# Charge_Discharge_Battery_Monitor_DC_DC_B.net
KiCad netlist of a schematic drawn in Altium Designer
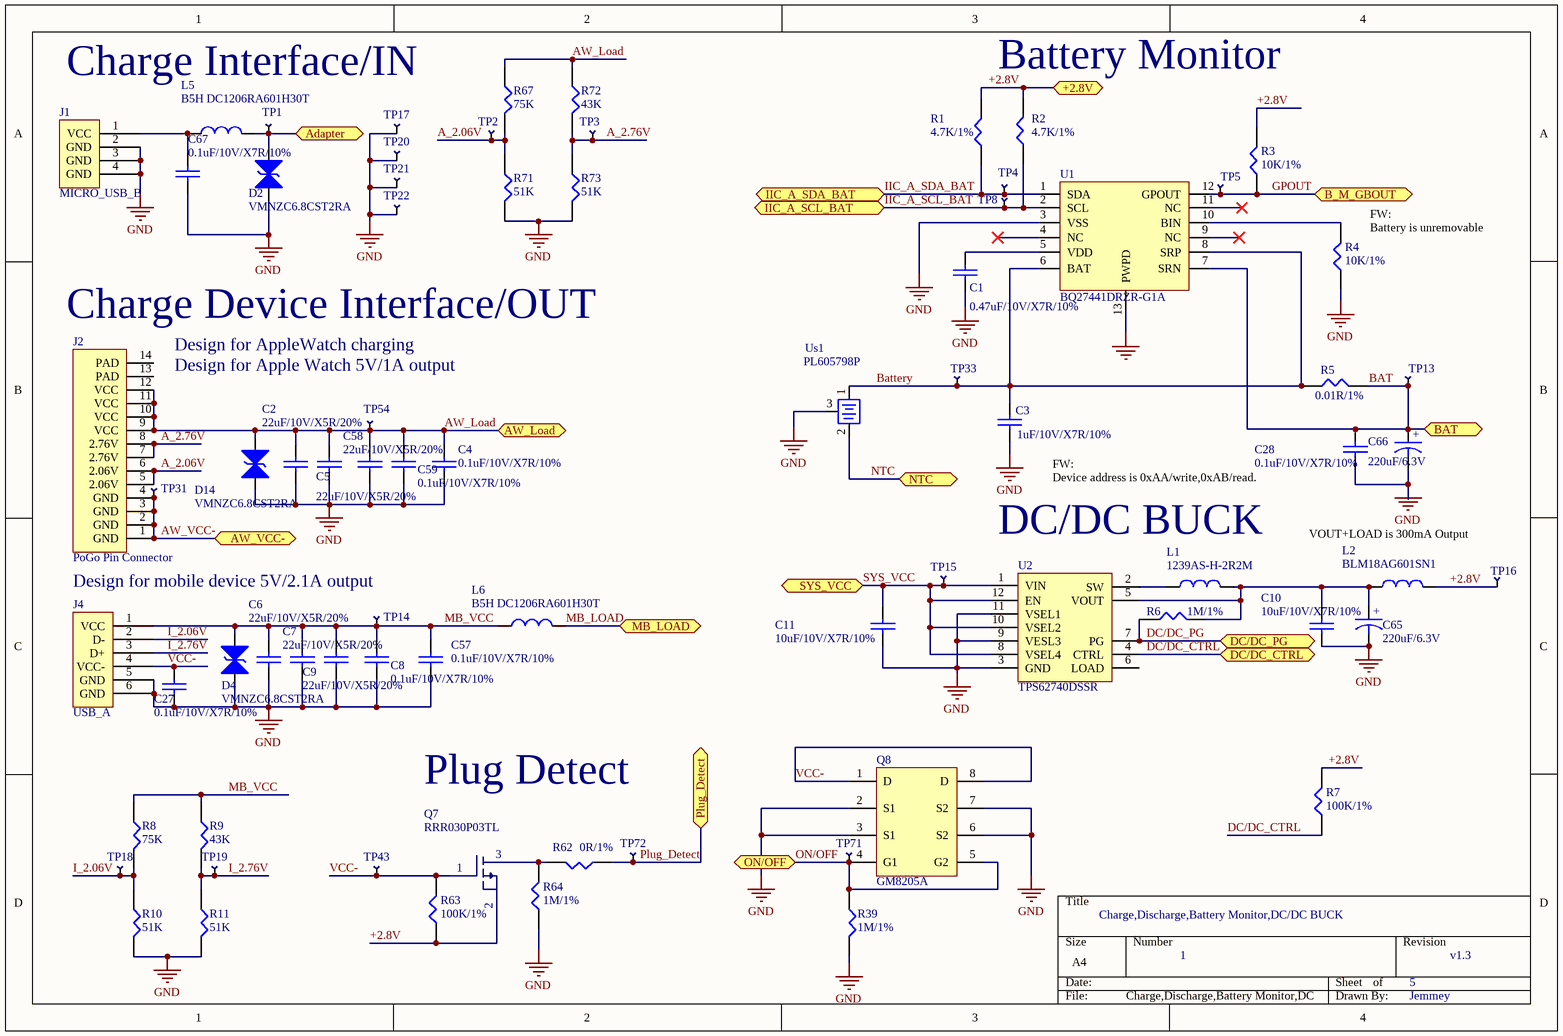
[diagram p0: Charge,Discharge,Battery Monitor,DC DC BUCK.SchDoc]

(export (version "E")
  (design (tool "Eeschema 10.0.6"))
  (components
    (comp (ref "C1")
      (value "0.47uF/10V/X7R/10%")
      (footprint "0402C")
      (description "厂家：Murata，型号：GRM155R71A474KE01D")
      (libsource (lib "*") (part "CAP"))
    )
    (comp (ref "C2")
      (value "22uF/10V/X5R/20%")
      (footprint "0603C")
      (description "厂家：Murata，型号：GRM188R61A226ME15D")
      (libsource (lib "*") (part "CAP"))
    )
    (comp (ref "C3")
      (value "1uF/10V/X7R/10%")
      (footprint "0402C")
      (description "厂家：Murata，型号：GRM155R61C105KA12D")
      (libsource (lib "*") (part "CAP"))
    )
    (comp (ref "C4")
      (value "0.1uF/10V/X7R/10%")
      (footprint "0402C")
      (description "厂家：Murata，型号：GRM155R71A104KA01D")
      (libsource (lib "*") (part "CAP"))
    )
    (comp (ref "C5")
      (value "22uF/10V/X5R/20%")
      (footprint "0603C")
      (description "厂家：Murata，型号：GRM188R61A226ME15D")
      (libsource (lib "*") (part "CAP"))
    )
    (comp (ref "C6")
      (value "22uF/10V/X5R/20%")
      (footprint "0603C")
      (description "厂家：Murata，型号：GRM188R61A226ME15D")
      (libsource (lib "*") (part "CAP"))
    )
    (comp (ref "C7")
      (value "22uF/10V/X5R/20%")
      (footprint "0603C")
      (description "厂家：Murata，型号：GRM188R61A226ME15D")
      (libsource (lib "*") (part "CAP"))
    )
    (comp (ref "C8")
      (value "0.1uF/10V/X7R/10%")
      (footprint "0402C")
      (description "厂家：Murata，型号：GRM155R71A104KA01D")
      (libsource (lib "*") (part "CAP"))
    )
    (comp (ref "C9")
      (value "22uF/10V/X5R/20%")
      (footprint "0603C")
      (description "厂家：Murata，型号：GRM188R61A226ME15D")
      (libsource (lib "*") (part "CAP"))
    )
    (comp (ref "C10")
      (value "10uF/10V/X7R/10%")
      (footprint "0603C")
      (description "厂家：Murata，型号：GRM188R61A106KE69D")
      (libsource (lib "*") (part "CAP"))
    )
    (comp (ref "C11")
      (value "10uF/10V/X7R/10%")
      (footprint "0603C")
      (description "厂家：Murata，型号：GRM188R61A106KE69D")
      (libsource (lib "*") (part "CAP"))
    )
    (comp (ref "C27")
      (value "0.1uF/10V/X7R/10%")
      (footprint "0402C")
      (description "厂家：Murata，型号：GRM155R71A104KA01D")
      (libsource (lib "*") (part "CAP"))
    )
    (comp (ref "C28")
      (value "0.1uF/10V/X7R/10%")
      (footprint "0402C")
      (description "厂家：Murata，型号：GRM155R71A104KA01D")
      (libsource (lib "*") (part "CAP"))
    )
    (comp (ref "C57")
      (value "0.1uF/10V/X7R/10%")
      (footprint "0402C")
      (description "厂家：Murata，型号：GRM155R71A104KA01D")
      (libsource (lib "*") (part "CAP"))
    )
    (comp (ref "C58")
      (value "22uF/10V/X5R/20%")
      (footprint "0603C")
      (description "厂家：Murata，型号：GRM188R61A226ME15D")
      (libsource (lib "*") (part "CAP"))
    )
    (comp (ref "C59")
      (value "0.1uF/10V/X7R/10%")
      (footprint "0402C")
      (description "厂家：Murata，型号：GRM155R71A104KA01D")
      (libsource (lib "*") (part "CAP"))
    )
    (comp (ref "C65")
      (value "220uF/6.3V")
      (footprint "3216")
      (description "厂家：ROHM，型号：TAJC227K010RNJ")
      (libsource (lib "MoJi LIB") (part "Capacitor"))
    )
    (comp (ref "C66")
      (value "220uF/6.3V")
      (footprint "3216")
      (description "厂家：ROHM，型号：TAJC227K010RNJ")
      (libsource (lib "MoJi LIB") (part "Capacitor"))
    )
    (comp (ref "C67")
      (value "0.1uF/10V/X7R/10%")
      (footprint "0402C")
      (description "厂家：Murata，型号：GRM155R71A104KA01D")
      (libsource (lib "*") (part "CAP"))
    )
    (comp (ref "D2")
      (value "VMNZC6.8CST2RA")
      (footprint "0402")
      (description "厂家：ROHM，型号：VMNZC6.8CST2RA")
      (libsource (lib "Amber") (part "ESD_1"))
    )
    (comp (ref "D4")
      (value "VMNZC6.8CST2RA")
      (footprint "0402")
      (description "厂家：ROHM，型号：VMNZC6.8CST2RA")
      (libsource (lib "Amber") (part "ESD_1"))
    )
    (comp (ref "D14")
      (value "VMNZC6.8CST2RA")
      (footprint "0402")
      (description "厂家：ROHM，型号：VMNZC6.8CST2RA")
      (libsource (lib "Amber") (part "ESD_1"))
    )
    (comp (ref "J1")
      (value "MICRO_USB_B")
      (footprint "Micro-USB-AVX-PAD")
      (description "厂家：AVX，型号：20-6751-005-001-007")
      (libsource (lib "Amber_Main_Board") (part "USB_B"))
    )
    (comp (ref "J2")
      (value "PoGo Pin Connector")
      (footprint "FPC_CON12-BACK-MOLEX")
      (description "厂家：MOLEX，型号：5034801200_sd")
      (libsource (lib "Amber_Main_Board") (part "PoGo Connector"))
    )
    (comp (ref "J4")
      (value "USB_A")
      (description "厂家：FCI，型号：87583")
      (libsource (lib "Amber_Main_Board") (part "USB_A"))
    )
    (comp (ref "L1")
      (value "1239AS-H-2R2M")
      (footprint "2520-TOKO")
      (description "厂家：Toko，型号1239AS-H-2R2M")
      (libsource (lib "Amber") (part "CHOKE"))
    )
    (comp (ref "L2")
      (value "BLM18AG601SN1")
      (footprint "0603R")
      (description "厂家：MURATA，型号：BLM18AG601SN1")
      (libsource (lib "Amber") (part "CHOKE"))
    )
    (comp (ref "L5")
      (value "B5H DC1206RA601H30T")
      (footprint "1206")
      (description "厂家：宇磁，型号：B5H DC1206RA601H30T")
      (libsource (lib "Amber") (part "CHOKE"))
    )
    (comp (ref "L6")
      (value "B5H DC1206RA601H30T")
      (footprint "1206")
      (description "厂家：宇磁，型号：B5H DC1206RA601H30T")
      (libsource (lib "Amber") (part "CHOKE"))
    )
    (comp (ref "Q7")
      (value "RRR030P03TL")
      (footprint "TSMT3")
      (description "厂家：ROHM，型号：RRR030P03TL")
      (libsource (lib "*") (part "PMOS"))
    )
    (comp (ref "Q8")
      (value "GM8205A")
      (footprint "TSSOP-8")
      (description "厂家：晶群科技，型号：GM8205A")
      (libsource (lib "Amber_Main_Board") (part "GM8205A"))
    )
    (comp (ref "R1")
      (value "4.7K/1%")
      (footprint "0402R")
      (description "厂家：Yageo，型号：RC0402FR-074K7L")
      (libsource (lib "*") (part "RES1"))
    )
    (comp (ref "R2")
      (value "4.7K/1%")
      (footprint "0402R")
      (description "厂家：Yageo，型号：RC0402FR-074K7L")
      (libsource (lib "*") (part "RES1"))
    )
    (comp (ref "R3")
      (value "10K/1%")
      (footprint "0402R")
      (description "厂家：Yageo，型号：RC0402FR-0710KL")
      (libsource (lib "*") (part "RES1"))
    )
    (comp (ref "R4")
      (value "10K/1%")
      (footprint "0402R")
      (description "厂家：Yageo，型号：RC0402FR-0710KL")
      (libsource (lib "*") (part "RES1"))
    )
    (comp (ref "R5")
      (value "0.01R/1%")
      (footprint "0805")
      (description "厂家：Yageo，型号：RL0805FR-070R01L")
      (libsource (lib "*") (part "RES1"))
    )
    (comp (ref "R6")
      (value "1M/1%")
      (footprint "0402R")
      (description "厂家：Yageo，型号：RC0402FR-071ML")
      (libsource (lib "*") (part "RES1"))
    )
    (comp (ref "R7")
      (value "100K/1%")
      (footprint "0402R")
      (description "厂家：Yageo，型号：RC0402FR-07100KL")
      (libsource (lib "*") (part "RES1"))
    )
    (comp (ref "R8")
      (value "75K")
      (footprint "0402R")
      (description "厂家：Yageo，型号：RC0402FR-0775KL")
      (libsource (lib "*") (part "RES1"))
    )
    (comp (ref "R9")
      (value "43K")
      (footprint "0402R")
      (description "厂家：Yageo，型号：RC0402FR-0743K9L")
      (libsource (lib "*") (part "RES1"))
    )
    (comp (ref "R10")
      (value "51K")
      (footprint "0402R")
      (description "厂家：Yageo，型号：RC0402FR-0751K9L")
      (libsource (lib "*") (part "RES1"))
    )
    (comp (ref "R11")
      (value "51K")
      (footprint "0402R")
      (description "厂家：Yageo，型号：RC0402FR-0751K9L")
      (libsource (lib "*") (part "RES1"))
    )
    (comp (ref "R39")
      (value "1M/1%")
      (footprint "0402R")
      (description "厂家：Yageo，型号：RC0402FR-071ML")
      (libsource (lib "*") (part "RES1"))
    )
    (comp (ref "R62")
      (value "0R/1%")
      (footprint "0402R")
      (description "厂家：Yageo，型号：RC0402FR-070RL")
      (libsource (lib "*") (part "RES1"))
    )
    (comp (ref "R63")
      (value "100K/1%")
      (footprint "0402R")
      (description "厂家：Yageo，型号：RC0402FR-07100KL")
      (libsource (lib "Schlib1") (part "RES"))
    )
    (comp (ref "R64")
      (value "1M/1%")
      (footprint "0402R")
      (description "厂家：Yageo，型号：RC0402FR-071ML")
      (libsource (lib "Schlib1") (part "RES"))
    )
    (comp (ref "R67")
      (value "75K")
      (footprint "0402R")
      (description "厂家：Yageo，型号：RC0402FR-0775KL")
      (libsource (lib "*") (part "RES1"))
    )
    (comp (ref "R71")
      (value "51K")
      (footprint "0402R")
      (description "厂家：Yageo，型号：RC0402FR-0751K9L")
      (libsource (lib "*") (part "RES1"))
    )
    (comp (ref "R72")
      (value "43K")
      (footprint "0402R")
      (description "厂家：Yageo，型号：RC0402FR-0743K9L")
      (libsource (lib "*") (part "RES1"))
    )
    (comp (ref "R73")
      (value "51K")
      (footprint "0402R")
      (description "厂家：Yageo，型号：RC0402FR-0751K9L")
      (libsource (lib "*") (part "RES1"))
    )
    (comp (ref "TP1")
      (value "TEST")
      (footprint "Test Pad")
      (description "Test Point")
      (libsource (lib "Amber") (part "TEST"))
    )
    (comp (ref "TP2")
      (value "TEST")
      (footprint "Test Pad")
      (description "Test Point")
      (libsource (lib "Amber") (part "TEST"))
    )
    (comp (ref "TP3")
      (value "TEST")
      (footprint "Test Pad")
      (description "Test Point")
      (libsource (lib "Amber") (part "TEST"))
    )
    (comp (ref "TP4")
      (value "TEST")
      (footprint "Test Pad")
      (description "Test Point")
      (libsource (lib "Amber") (part "TEST"))
    )
    (comp (ref "TP5")
      (value "TEST")
      (footprint "Test Pad")
      (description "Test Point")
      (libsource (lib "Amber") (part "TEST"))
    )
    (comp (ref "TP8")
      (value "TEST")
      (footprint "Test Pad")
      (description "Test Point")
      (libsource (lib "Amber") (part "TEST"))
    )
    (comp (ref "TP13")
      (value "TEST")
      (footprint "Test Pad")
      (description "Test Point")
      (libsource (lib "Amber") (part "TEST"))
    )
    (comp (ref "TP14")
      (value "TEST")
      (footprint "Test Pad")
      (description "Test Point")
      (libsource (lib "Amber") (part "TEST"))
    )
    (comp (ref "TP15")
      (value "TEST")
      (footprint "Test Pad")
      (description "Test Point")
      (libsource (lib "Amber") (part "TEST"))
    )
    (comp (ref "TP16")
      (value "TEST")
      (footprint "Test Pad")
      (description "Test Point")
      (libsource (lib "Amber") (part "TEST"))
    )
    (comp (ref "TP17")
      (value "TEST")
      (footprint "Test Pad")
      (description "Test Point")
      (libsource (lib "Amber") (part "TEST"))
    )
    (comp (ref "TP18")
      (value "TEST")
      (footprint "Test Pad")
      (description "Test Point")
      (libsource (lib "Amber") (part "TEST"))
    )
    (comp (ref "TP19")
      (value "TEST")
      (footprint "Test Pad")
      (description "Test Point")
      (libsource (lib "Amber") (part "TEST"))
    )
    (comp (ref "TP20")
      (value "TEST")
      (footprint "Test Pad")
      (description "Test Point")
      (libsource (lib "Amber") (part "TEST"))
    )
    (comp (ref "TP21")
      (value "TEST")
      (footprint "Test Pad")
      (description "Test Point")
      (libsource (lib "Amber") (part "TEST"))
    )
    (comp (ref "TP22")
      (value "TEST")
      (footprint "Test Pad")
      (description "Test Point")
      (libsource (lib "Amber") (part "TEST"))
    )
    (comp (ref "TP31")
      (value "TEST")
      (footprint "Test Pad")
      (description "Test Point")
      (libsource (lib "Amber") (part "TEST"))
    )
    (comp (ref "TP33")
      (value "TEST")
      (footprint "Test Pad")
      (description "Test Point")
      (libsource (lib "Amber") (part "TEST"))
    )
    (comp (ref "TP43")
      (value "TEST")
      (footprint "Test Pad")
      (description "Test Point")
      (libsource (lib "Amber") (part "TEST"))
    )
    (comp (ref "TP54")
      (value "TEST")
      (footprint "Test Pad")
      (description "Test Point")
      (libsource (lib "Amber") (part "TEST"))
    )
    (comp (ref "TP71")
      (value "TEST")
      (footprint "Test Pad")
      (description "Test Point")
      (libsource (lib "Amber") (part "TEST"))
    )
    (comp (ref "TP72")
      (value "TEST")
      (footprint "Test Pad")
      (description "Test Point")
      (libsource (lib "Amber") (part "TEST"))
    )
    (comp (ref "U1")
      (value "BQ27441DRZR-G1A")
      (footprint "DRZ")
      (description "厂家：TI，型号：BQ27441DRZR-G1A")
      (libsource (lib "Centrol Control Panel(20140910)") (part "Bq27411"))
    )
    (comp (ref "U2")
      (value "TPS62740DSSR")
      (footprint "DSS")
      (description "厂家：TI，型号：TPS62740DSSR")
      (libsource (lib "Amber") (part "TPS62740"))
    )
    (comp (ref "Us1")
      (value "PL605798P")
      (footprint "Battery")
      (description "厂家：红亚山，型号：PL605798P")
      (libsource (lib "Amber") (part "BAT"))
    )
  )
  (nets
    (net (code "1") (name "/+2.8V") (class "Default")
      (node (ref "L2") (pin "2") (pinfunction "2_2") (pintype "passive"))
      (node (ref "Q7") (pin "2") (pinfunction "S_2") (pintype "passive"))
      (node (ref "R1") (pin "2") (pinfunction "2_2") (pintype "passive"))
      (node (ref "R2") (pin "2") (pinfunction "2_2") (pintype "passive"))
      (node (ref "R3") (pin "2") (pinfunction "2_2") (pintype "passive"))
      (node (ref "R63") (pin "1") (pinfunction "1_1") (pintype "passive"))
      (node (ref "R7") (pin "2") (pinfunction "2_2") (pintype "passive"))
      (node (ref "TP16") (pin "1") (pinfunction "1_1") (pintype "passive"))
    )
    (net (code "2") (name "/AW_Load") (class "Default")
      (node (ref "C2") (pin "1") (pinfunction "1_1") (pintype "passive"))
      (node (ref "C4") (pin "1") (pinfunction "1_1") (pintype "passive"))
      (node (ref "C5") (pin "1") (pinfunction "1_1") (pintype "passive"))
      (node (ref "C58") (pin "1") (pinfunction "1_1") (pintype "passive"))
      (node (ref "C59") (pin "1") (pinfunction "1_1") (pintype "passive"))
      (node (ref "D14") (pin "2") (pinfunction "dIode2_2") (pintype "passive"))
      (node (ref "J2") (pin "10") (pinfunction "VCC_10") (pintype "passive"))
      (node (ref "J2") (pin "11") (pinfunction "VCC_11") (pintype "passive"))
      (node (ref "J2") (pin "12") (pinfunction "VCC_12") (pintype "passive"))
      (node (ref "J2") (pin "9") (pinfunction "VCC_9") (pintype "passive"))
      (node (ref "R67") (pin "1") (pinfunction "1_1") (pintype "passive"))
      (node (ref "R72") (pin "1") (pinfunction "1_1") (pintype "passive"))
      (node (ref "TP54") (pin "1") (pinfunction "1_1") (pintype "passive"))
    )
    (net (code "3") (name "/AW_VCC-") (class "Default")
      (node (ref "J2") (pin "1") (pinfunction "GND_1") (pintype "passive"))
      (node (ref "J2") (pin "2") (pinfunction "GND_2") (pintype "passive"))
      (node (ref "J2") (pin "3") (pinfunction "GND_3") (pintype "passive"))
      (node (ref "J2") (pin "4") (pinfunction "GND_4") (pintype "passive"))
      (node (ref "TP31") (pin "1") (pinfunction "1_1") (pintype "passive"))
    )
    (net (code "4") (name "/A_2.06V") (class "Default")
      (node (ref "J2") (pin "5") (pinfunction "2.06V_5") (pintype "passive"))
      (node (ref "J2") (pin "6") (pinfunction "2.06V_6") (pintype "passive"))
      (node (ref "R67") (pin "2") (pinfunction "2_2") (pintype "passive"))
      (node (ref "R71") (pin "1") (pinfunction "1_1") (pintype "passive"))
      (node (ref "TP2") (pin "1") (pinfunction "1_1") (pintype "passive"))
    )
    (net (code "5") (name "/A_2.76V") (class "Default")
      (node (ref "J2") (pin "7") (pinfunction "2.76V_7") (pintype "passive"))
      (node (ref "J2") (pin "8") (pinfunction "2.76V_8") (pintype "passive"))
      (node (ref "R72") (pin "2") (pinfunction "2_2") (pintype "passive"))
      (node (ref "R73") (pin "1") (pinfunction "1_1") (pintype "passive"))
      (node (ref "TP3") (pin "1") (pinfunction "1_1") (pintype "passive"))
    )
    (net (code "6") (name "/Adapter") (class "Default")
      (node (ref "D2") (pin "2") (pinfunction "dIode2_2") (pintype "passive"))
      (node (ref "L5") (pin "2") (pinfunction "2_2") (pintype "passive"))
      (node (ref "TP1") (pin "1") (pinfunction "1_1") (pintype "passive"))
    )
    (net (code "7") (name "/BAT") (class "Default")
      (node (ref "C28") (pin "1") (pinfunction "1_1") (pintype "passive"))
      (node (ref "C66") (pin "1") (pinfunction "1_1") (pintype "passive"))
      (node (ref "R5") (pin "2") (pinfunction "2_2") (pintype "passive"))
      (node (ref "TP13") (pin "1") (pinfunction "1_1") (pintype "passive"))
      (node (ref "U1") (pin "7") (pinfunction "SRN_7") (pintype "passive"))
    )
    (net (code "8") (name "/Battery") (class "Default")
      (node (ref "C3") (pin "1") (pinfunction "1_1") (pintype "passive"))
      (node (ref "R5") (pin "1") (pinfunction "1_1") (pintype "passive"))
      (node (ref "TP33") (pin "1") (pinfunction "1_1") (pintype "passive"))
      (node (ref "U1") (pin "6") (pinfunction "BAT_6") (pintype "passive"))
      (node (ref "U1") (pin "8") (pinfunction "SRP_8") (pintype "passive"))
      (node (ref "Us1") (pin "1") (pinfunction "VCC_1") (pintype "passive"))
    )
    (net (code "9") (name "/DC{slash}DC_CTRL") (class "Default")
      (node (ref "R7") (pin "1") (pinfunction "1_1") (pintype "passive"))
      (node (ref "U2") (pin "4") (pinfunction "CTRL_4") (pintype "passive"))
    )
    (net (code "10") (name "/DC{slash}DC_PG") (class "Default")
      (node (ref "R6") (pin "1") (pinfunction "1_1") (pintype "passive"))
      (node (ref "U2") (pin "7") (pinfunction "PG_7") (pintype "passive"))
    )
    (net (code "11") (name "/GPOUT") (class "Default")
      (node (ref "R3") (pin "1") (pinfunction "1_1") (pintype "passive"))
      (node (ref "TP5") (pin "1") (pinfunction "1_1") (pintype "passive"))
      (node (ref "U1") (pin "12") (pinfunction "GPOUT_12") (pintype "passive"))
    )
    (net (code "12") (name "/IIC_A_SCL_BAT") (class "Default")
      (node (ref "R2") (pin "1") (pinfunction "1_1") (pintype "passive"))
      (node (ref "TP8") (pin "1") (pinfunction "1_1") (pintype "passive"))
      (node (ref "U1") (pin "2") (pinfunction "SCL_2") (pintype "passive"))
    )
    (net (code "13") (name "/IIC_A_SDA_BAT") (class "Default")
      (node (ref "R1") (pin "1") (pinfunction "1_1") (pintype "passive"))
      (node (ref "TP4") (pin "1") (pinfunction "1_1") (pintype "passive"))
      (node (ref "U1") (pin "1") (pinfunction "SDA_1") (pintype "passive"))
    )
    (net (code "14") (name "/I_2.06V") (class "Default")
      (node (ref "J4") (pin "2") (pinfunction "D-_2") (pintype "passive"))
      (node (ref "R10") (pin "1") (pinfunction "1_1") (pintype "passive"))
      (node (ref "R8") (pin "2") (pinfunction "2_2") (pintype "passive"))
      (node (ref "TP18") (pin "1") (pinfunction "1_1") (pintype "passive"))
    )
    (net (code "15") (name "/I_2.76V") (class "Default")
      (node (ref "J4") (pin "3") (pinfunction "D+_3") (pintype "passive"))
      (node (ref "R11") (pin "1") (pinfunction "1_1") (pintype "passive"))
      (node (ref "R9") (pin "2") (pinfunction "2_2") (pintype "passive"))
      (node (ref "TP19") (pin "1") (pinfunction "1_1") (pintype "passive"))
    )
    (net (code "16") (name "/MB_LOAD") (class "Default")
      (node (ref "L6") (pin "2") (pinfunction "2_2") (pintype "passive"))
    )
    (net (code "17") (name "/MB_VCC") (class "Default")
      (node (ref "C57") (pin "1") (pinfunction "1_1") (pintype "passive"))
      (node (ref "C6") (pin "1") (pinfunction "1_1") (pintype "passive"))
      (node (ref "C7") (pin "1") (pinfunction "1_1") (pintype "passive"))
      (node (ref "C8") (pin "1") (pinfunction "1_1") (pintype "passive"))
      (node (ref "C9") (pin "1") (pinfunction "1_1") (pintype "passive"))
      (node (ref "D4") (pin "2") (pinfunction "dIode2_2") (pintype "passive"))
      (node (ref "J4") (pin "1") (pinfunction "VCC_1") (pintype "passive"))
      (node (ref "L6") (pin "1") (pinfunction "1_1") (pintype "passive"))
      (node (ref "R8") (pin "1") (pinfunction "1_1") (pintype "passive"))
      (node (ref "R9") (pin "1") (pinfunction "1_1") (pintype "passive"))
      (node (ref "TP14") (pin "1") (pinfunction "1_1") (pintype "passive"))
    )
    (net (code "18") (name "/NTC") (class "Default")
      (node (ref "Us1") (pin "2") (pinfunction "NTC_2") (pintype "passive"))
    )
    (net (code "19") (name "/ON{slash}OFF") (class "Default")
      (node (ref "Q8") (pin "4") (pinfunction "G1_4") (pintype "passive"))
      (node (ref "Q8") (pin "5") (pinfunction "G2_5") (pintype "passive"))
      (node (ref "R39") (pin "1") (pinfunction "1_1") (pintype "passive"))
      (node (ref "TP71") (pin "1") (pinfunction "1_1") (pintype "passive"))
    )
    (net (code "20") (name "/Plug_Detect") (class "Default")
      (node (ref "R62") (pin "1") (pinfunction "1_1") (pintype "passive"))
      (node (ref "TP72") (pin "1") (pinfunction "1_1") (pintype "passive"))
    )
    (net (code "21") (name "/SYS_VCC") (class "Default")
      (node (ref "C11") (pin "1") (pinfunction "1_1") (pintype "passive"))
      (node (ref "TP15") (pin "1") (pinfunction "1_1") (pintype "passive"))
      (node (ref "U2") (pin "1") (pinfunction "VIN_1") (pintype "passive"))
      (node (ref "U2") (pin "10") (pinfunction "VSEL2_10") (pintype "passive"))
      (node (ref "U2") (pin "12") (pinfunction "EN_12") (pintype "passive"))
      (node (ref "U2") (pin "8") (pinfunction "VSEL4_8") (pintype "passive"))
    )
    (net (code "22") (name "/VCC-") (class "Default")
      (node (ref "C27") (pin "1") (pinfunction "1_1") (pintype "passive"))
      (node (ref "J4") (pin "4") (pinfunction "VCC-_4") (pintype "passive"))
      (node (ref "Q7") (pin "1") (pinfunction "G_1") (pintype "passive"))
      (node (ref "Q8") (pin "1") (pinfunction "D_1") (pintype "passive"))
      (node (ref "Q8") (pin "8") (pinfunction "D_8") (pintype "passive"))
      (node (ref "R63") (pin "2") (pinfunction "2_2") (pintype "passive"))
      (node (ref "TP43") (pin "1") (pinfunction "1_1") (pintype "passive"))
    )
    (net (code "23") (name "GND") (class "Default")
      (node (ref "C1") (pin "2") (pinfunction "2_2") (pintype "passive"))
      (node (ref "C10") (pin "2") (pinfunction "2_2") (pintype "passive"))
      (node (ref "C11") (pin "2") (pinfunction "2_2") (pintype "passive"))
      (node (ref "C2") (pin "2") (pinfunction "2_2") (pintype "passive"))
      (node (ref "C27") (pin "2") (pinfunction "2_2") (pintype "passive"))
      (node (ref "C28") (pin "2") (pinfunction "2_2") (pintype "passive"))
      (node (ref "C3") (pin "2") (pinfunction "2_2") (pintype "passive"))
      (node (ref "C4") (pin "2") (pinfunction "2_2") (pintype "passive"))
      (node (ref "C5") (pin "2") (pinfunction "2_2") (pintype "passive"))
      (node (ref "C57") (pin "2") (pinfunction "2_2") (pintype "passive"))
      (node (ref "C58") (pin "2") (pinfunction "2_2") (pintype "passive"))
      (node (ref "C59") (pin "2") (pinfunction "2_2") (pintype "passive"))
      (node (ref "C6") (pin "2") (pinfunction "2_2") (pintype "passive"))
      (node (ref "C65") (pin "2") (pinfunction "2_2") (pintype "passive"))
      (node (ref "C66") (pin "2") (pinfunction "2_2") (pintype "passive"))
      (node (ref "C67") (pin "2") (pinfunction "2_2") (pintype "passive"))
      (node (ref "C7") (pin "2") (pinfunction "2_2") (pintype "passive"))
      (node (ref "C8") (pin "2") (pinfunction "2_2") (pintype "passive"))
      (node (ref "C9") (pin "2") (pinfunction "2_2") (pintype "passive"))
      (node (ref "D14") (pin "1") (pinfunction "Diode1_1") (pintype "passive"))
      (node (ref "D2") (pin "1") (pinfunction "Diode1_1") (pintype "passive"))
      (node (ref "D4") (pin "1") (pinfunction "Diode1_1") (pintype "passive"))
      (node (ref "J1") (pin "2") (pinfunction "GND_2") (pintype "passive"))
      (node (ref "J1") (pin "3") (pinfunction "GND_3") (pintype "passive"))
      (node (ref "J1") (pin "4") (pinfunction "GND_4") (pintype "passive"))
      (node (ref "J4") (pin "5") (pinfunction "GND_5") (pintype "passive"))
      (node (ref "J4") (pin "6") (pinfunction "GND_6") (pintype "passive"))
      (node (ref "Q8") (pin "2") (pinfunction "S1_2") (pintype "passive"))
      (node (ref "Q8") (pin "3") (pinfunction "S1_3") (pintype "passive"))
      (node (ref "Q8") (pin "6") (pinfunction "S2_6") (pintype "passive"))
      (node (ref "Q8") (pin "7") (pinfunction "S2_7") (pintype "passive"))
      (node (ref "R10") (pin "2") (pinfunction "2_2") (pintype "passive"))
      (node (ref "R11") (pin "2") (pinfunction "2_2") (pintype "passive"))
      (node (ref "R39") (pin "2") (pinfunction "2_2") (pintype "passive"))
      (node (ref "R4") (pin "1") (pinfunction "1_1") (pintype "passive"))
      (node (ref "R64") (pin "1") (pinfunction "1_1") (pintype "passive"))
      (node (ref "R71") (pin "2") (pinfunction "2_2") (pintype "passive"))
      (node (ref "R73") (pin "2") (pinfunction "2_2") (pintype "passive"))
      (node (ref "TP17") (pin "1") (pinfunction "1_1") (pintype "passive"))
      (node (ref "TP20") (pin "1") (pinfunction "1_1") (pintype "passive"))
      (node (ref "TP21") (pin "1") (pinfunction "1_1") (pintype "passive"))
      (node (ref "TP22") (pin "1") (pinfunction "1_1") (pintype "passive"))
      (node (ref "U1") (pin "13") (pinfunction "PWPD_13") (pintype "passive"))
      (node (ref "U1") (pin "3") (pinfunction "VSS_3") (pintype "passive"))
      (node (ref "U2") (pin "11") (pinfunction "VSEL1_11") (pintype "passive"))
      (node (ref "U2") (pin "3") (pinfunction "GND_3") (pintype "passive"))
      (node (ref "U2") (pin "9") (pinfunction "VESL3_9") (pintype "passive"))
      (node (ref "Us1") (pin "3") (pinfunction "GND_3") (pintype "passive"))
    )
    (net (code "24") (name "Net-(J1-VCC)") (class "Default")
      (node (ref "C67") (pin "1") (pinfunction "1_1") (pintype "passive"))
      (node (ref "J1") (pin "1") (pinfunction "VCC_1") (pintype "passive"))
      (node (ref "L5") (pin "1") (pinfunction "1_1") (pintype "passive"))
    )
    (net (code "25") (name "Net-(Q7-D)") (class "Default")
      (node (ref "Q7") (pin "3") (pinfunction "D_3") (pintype "passive"))
      (node (ref "R62") (pin "2") (pinfunction "2_2") (pintype "passive"))
      (node (ref "R64") (pin "2") (pinfunction "2_2") (pintype "passive"))
    )
    (net (code "26") (name "Net-(U1-BIN)") (class "Default")
      (node (ref "R4") (pin "2") (pinfunction "2_2") (pintype "passive"))
      (node (ref "U1") (pin "10") (pinfunction "BIN_10") (pintype "passive"))
    )
    (net (code "27") (name "Net-(U1-VDD)") (class "Default")
      (node (ref "C1") (pin "1") (pinfunction "1_1") (pintype "passive"))
      (node (ref "U1") (pin "5") (pinfunction "VDD_5") (pintype "passive"))
    )
    (net (code "28") (name "Net-(U2-SW)") (class "Default")
      (node (ref "L1") (pin "1") (pinfunction "1_1") (pintype "passive"))
      (node (ref "U2") (pin "2") (pinfunction "SW_2") (pintype "passive"))
    )
    (net (code "29") (name "Net-(U2-VOUT)") (class "Default")
      (node (ref "C10") (pin "1") (pinfunction "1_1") (pintype "passive"))
      (node (ref "C65") (pin "1") (pinfunction "1_1") (pintype "passive"))
      (node (ref "L1") (pin "2") (pinfunction "2_2") (pintype "passive"))
      (node (ref "L2") (pin "1") (pinfunction "1_1") (pintype "passive"))
      (node (ref "R6") (pin "2") (pinfunction "2_2") (pintype "passive"))
      (node (ref "U2") (pin "5") (pinfunction "VOUT_5") (pintype "passive"))
    )
    (net (code "30") (name "unconnected-(J2-PAD-Pad13)") (class "Default")
      (node (ref "J2") (pin "13") (pinfunction "PAD_13") (pintype "passive"))
    )
    (net (code "31") (name "unconnected-(J2-PAD-Pad14)") (class "Default")
      (node (ref "J2") (pin "14") (pinfunction "PAD_14") (pintype "passive"))
    )
    (net (code "32") (name "unconnected-(U1-NC-Pad4)") (class "Default")
      (node (ref "U1") (pin "4") (pinfunction "NC_4") (pintype "passive+no_connect"))
    )
    (net (code "33") (name "unconnected-(U1-NC-Pad9)") (class "Default")
      (node (ref "U1") (pin "9") (pinfunction "NC_9") (pintype "passive+no_connect"))
    )
    (net (code "34") (name "unconnected-(U1-NC-Pad11)") (class "Default")
      (node (ref "U1") (pin "11") (pinfunction "NC_11") (pintype "passive+no_connect"))
    )
    (net (code "35") (name "unconnected-(U2-LOAD-Pad6)") (class "Default")
      (node (ref "U2") (pin "6") (pinfunction "LOAD_6") (pintype "passive"))
    )
  )
)
